# Ethernet_Module.net
KiCad netlist of a schematic drawn in Altium Designer
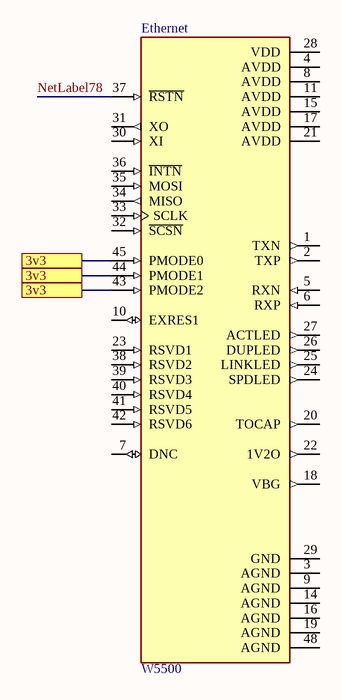
[diagram p0: Ethernet Module.SchDoc]

(export (version "E")
  (design (tool "Eeschema 10.0.6"))
  (components
    (comp (ref "Ethernet")
      (value "W5500")
      (footprint "QFP50P900X900X160-48N")
      (description "Ethernet Controller 10/100 Base-T/TX PHY SPI Interface 48-LQFP (7x7)")
      (fields (field (name "MF") "WIZnet"))
      (libsource (lib "W5500") (part "W5500"))
    )
  )
  (nets
    (net (code "1") (name "/3v3") (class "Default")
      (node (ref "Ethernet") (pin "43") (pinfunction "PMODE2_43") (pintype "input"))
      (node (ref "Ethernet") (pin "44") (pinfunction "PMODE1_44") (pintype "input"))
      (node (ref "Ethernet") (pin "45") (pinfunction "PMODE0_45") (pintype "input"))
    )
    (net (code "2") (name "/NetLabel78") (class "Default")
      (node (ref "Ethernet") (pin "37") (pinfunction "~{RSTN}_37") (pintype "input"))
    )
    (net (code "3") (name "unconnected-(Ethernet-1V2O-Pad22)") (class "Default")
      (node (ref "Ethernet") (pin "22") (pinfunction "1V2O_22") (pintype "output"))
    )
    (net (code "4") (name "unconnected-(Ethernet-ACTLED-Pad27)") (class "Default")
      (node (ref "Ethernet") (pin "27") (pinfunction "ACTLED_27") (pintype "output"))
    )
    (net (code "5") (name "unconnected-(Ethernet-AGND-Pad3)") (class "Default")
      (node (ref "Ethernet") (pin "3") (pinfunction "AGND_3") (pintype "power_in"))
    )
    (net (code "6") (name "unconnected-(Ethernet-AGND-Pad9)") (class "Default")
      (node (ref "Ethernet") (pin "9") (pinfunction "AGND_9") (pintype "power_in"))
    )
    (net (code "7") (name "unconnected-(Ethernet-AGND-Pad14)") (class "Default")
      (node (ref "Ethernet") (pin "14") (pinfunction "AGND_14") (pintype "power_in"))
    )
    (net (code "8") (name "unconnected-(Ethernet-AGND-Pad16)") (class "Default")
      (node (ref "Ethernet") (pin "16") (pinfunction "AGND_16") (pintype "power_in"))
    )
    (net (code "9") (name "unconnected-(Ethernet-AGND-Pad19)") (class "Default")
      (node (ref "Ethernet") (pin "19") (pinfunction "AGND_19") (pintype "power_in"))
    )
    (net (code "10") (name "unconnected-(Ethernet-AGND-Pad48)") (class "Default")
      (node (ref "Ethernet") (pin "48") (pinfunction "AGND_48") (pintype "power_in"))
    )
    (net (code "11") (name "unconnected-(Ethernet-AVDD-Pad4)") (class "Default")
      (node (ref "Ethernet") (pin "4") (pinfunction "AVDD_4") (pintype "power_in"))
    )
    (net (code "12") (name "unconnected-(Ethernet-AVDD-Pad8)") (class "Default")
      (node (ref "Ethernet") (pin "8") (pinfunction "AVDD_8") (pintype "power_in"))
    )
    (net (code "13") (name "unconnected-(Ethernet-AVDD-Pad11)") (class "Default")
      (node (ref "Ethernet") (pin "11") (pinfunction "AVDD_11") (pintype "power_in"))
    )
    (net (code "14") (name "unconnected-(Ethernet-AVDD-Pad15)") (class "Default")
      (node (ref "Ethernet") (pin "15") (pinfunction "AVDD_15") (pintype "power_in"))
    )
    (net (code "15") (name "unconnected-(Ethernet-AVDD-Pad17)") (class "Default")
      (node (ref "Ethernet") (pin "17") (pinfunction "AVDD_17") (pintype "power_in"))
    )
    (net (code "16") (name "unconnected-(Ethernet-AVDD-Pad21)") (class "Default")
      (node (ref "Ethernet") (pin "21") (pinfunction "AVDD_21") (pintype "power_in"))
    )
    (net (code "17") (name "unconnected-(Ethernet-DNC-Pad7)") (class "Default")
      (node (ref "Ethernet") (pin "7") (pinfunction "DNC_7") (pintype "bidirectional"))
    )
    (net (code "18") (name "unconnected-(Ethernet-DUPLED-Pad26)") (class "Default")
      (node (ref "Ethernet") (pin "26") (pinfunction "DUPLED_26") (pintype "output"))
    )
    (net (code "19") (name "unconnected-(Ethernet-EXRES1-Pad10)") (class "Default")
      (node (ref "Ethernet") (pin "10") (pinfunction "EXRES1_10") (pintype "bidirectional"))
    )
    (net (code "20") (name "unconnected-(Ethernet-GND-Pad29)") (class "Default")
      (node (ref "Ethernet") (pin "29") (pinfunction "GND_29") (pintype "passive"))
    )
    (net (code "21") (name "unconnected-(Ethernet-LINKLED-Pad25)") (class "Default")
      (node (ref "Ethernet") (pin "25") (pinfunction "LINKLED_25") (pintype "output"))
    )
    (net (code "22") (name "unconnected-(Ethernet-MISO-Pad34)") (class "Default")
      (node (ref "Ethernet") (pin "34") (pinfunction "MISO_34") (pintype "output"))
    )
    (net (code "23") (name "unconnected-(Ethernet-MOSI-Pad35)") (class "Default")
      (node (ref "Ethernet") (pin "35") (pinfunction "MOSI_35") (pintype "input"))
    )
    (net (code "24") (name "unconnected-(Ethernet-RSVD1-Pad23)") (class "Default")
      (node (ref "Ethernet") (pin "23") (pinfunction "RSVD1_23") (pintype "input"))
    )
    (net (code "25") (name "unconnected-(Ethernet-RSVD2-Pad38)") (class "Default")
      (node (ref "Ethernet") (pin "38") (pinfunction "RSVD2_38") (pintype "input"))
    )
    (net (code "26") (name "unconnected-(Ethernet-RSVD3-Pad39)") (class "Default")
      (node (ref "Ethernet") (pin "39") (pinfunction "RSVD3_39") (pintype "input"))
    )
    (net (code "27") (name "unconnected-(Ethernet-RSVD4-Pad40)") (class "Default")
      (node (ref "Ethernet") (pin "40") (pinfunction "RSVD4_40") (pintype "input"))
    )
    (net (code "28") (name "unconnected-(Ethernet-RSVD5-Pad41)") (class "Default")
      (node (ref "Ethernet") (pin "41") (pinfunction "RSVD5_41") (pintype "input"))
    )
    (net (code "29") (name "unconnected-(Ethernet-RSVD6-Pad42)") (class "Default")
      (node (ref "Ethernet") (pin "42") (pinfunction "RSVD6_42") (pintype "input"))
    )
    (net (code "30") (name "unconnected-(Ethernet-RXN-Pad5)") (class "Default")
      (node (ref "Ethernet") (pin "5") (pinfunction "RXN_5") (pintype "input"))
    )
    (net (code "31") (name "unconnected-(Ethernet-RXP-Pad6)") (class "Default")
      (node (ref "Ethernet") (pin "6") (pinfunction "RXP_6") (pintype "input"))
    )
    (net (code "32") (name "unconnected-(Ethernet-SCLK-Pad33)") (class "Default")
      (node (ref "Ethernet") (pin "33") (pinfunction "SCLK_33") (pintype "input"))
    )
    (net (code "33") (name "unconnected-(Ethernet-SPDLED-Pad24)") (class "Default")
      (node (ref "Ethernet") (pin "24") (pinfunction "SPDLED_24") (pintype "output"))
    )
    (net (code "34") (name "unconnected-(Ethernet-TOCAP-Pad20)") (class "Default")
      (node (ref "Ethernet") (pin "20") (pinfunction "TOCAP_20") (pintype "output"))
    )
    (net (code "35") (name "unconnected-(Ethernet-TXN-Pad1)") (class "Default")
      (node (ref "Ethernet") (pin "1") (pinfunction "TXN_1") (pintype "output"))
    )
    (net (code "36") (name "unconnected-(Ethernet-TXP-Pad2)") (class "Default")
      (node (ref "Ethernet") (pin "2") (pinfunction "TXP_2") (pintype "output"))
    )
    (net (code "37") (name "unconnected-(Ethernet-VBG-Pad18)") (class "Default")
      (node (ref "Ethernet") (pin "18") (pinfunction "VBG_18") (pintype "output"))
    )
    (net (code "38") (name "unconnected-(Ethernet-VDD-Pad28)") (class "Default")
      (node (ref "Ethernet") (pin "28") (pinfunction "VDD_28") (pintype "power_in"))
    )
    (net (code "39") (name "unconnected-(Ethernet-XI-Pad30)") (class "Default")
      (node (ref "Ethernet") (pin "30") (pinfunction "XI_30") (pintype "input"))
    )
    (net (code "40") (name "unconnected-(Ethernet-XO-Pad31)") (class "Default")
      (node (ref "Ethernet") (pin "31") (pinfunction "XO_31") (pintype "output"))
    )
    (net (code "41") (name "unconnected-(Ethernet-~{INTN}-Pad36)") (class "Default")
      (node (ref "Ethernet") (pin "36") (pinfunction "~{INTN}_36") (pintype "input"))
    )
    (net (code "42") (name "unconnected-(Ethernet-~{SCSN}-Pad32)") (class "Default")
      (node (ref "Ethernet") (pin "32") (pinfunction "~{SCSN}_32") (pintype "input"))
    )
  )
)
